# Sheet2-power.net
KiCad netlist of a schematic drawn in Altium Designer
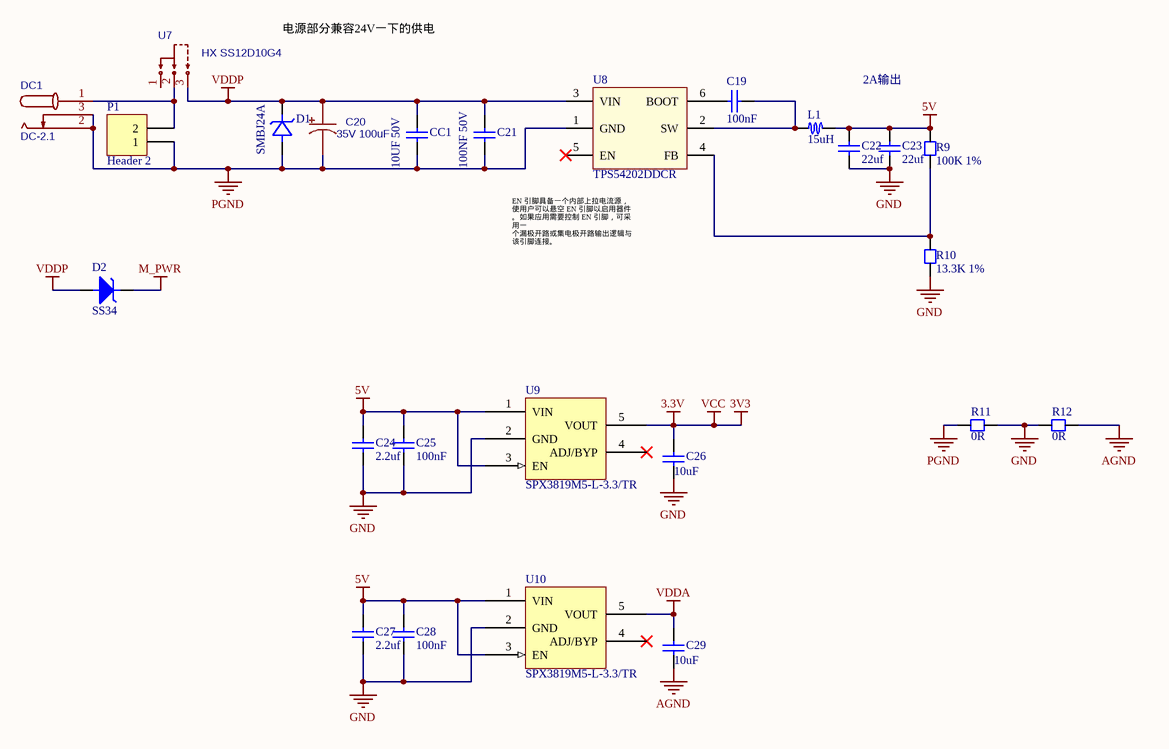
[diagram p0: Sheet2-power.SchDoc]

(export (version "E")
  (design (tool "Eeschema 10.0.6"))
  (components
    (comp (ref "C19")
      (value "100nF")
      (footprint "CC1608-0603")
      (description "0603封装的电容")
      (fields (field (name "PUBLISHER") "Altium Limited"))
      (libsource (lib "base") (part "Cap Chip 0603"))
    )
    (comp (ref "C20")
      (value "35V 100uF")
      (footprint "CAP-SMD_D6.3")
      (description "铝点解电容")
      (fields
        (field (name "BOM_SUPPLIER PART") "C413527")
        (field (name "BOM_MANUFACTURER PART") "EEEFP1C681AP")
        (field (name "CONTRIBUTOR") "LCSC")
      )
      (libsource (lib "base") (part "Cap ECAP SMD"))
    )
    (comp (ref "C21")
      (value "100NF 50V")
      (footprint "CC1608-0603")
      (description "0603封装的电容")
      (fields (field (name "PUBLISHER") "Altium Limited"))
      (libsource (lib "base") (part "Cap Chip 0603"))
    )
    (comp (ref "C22")
      (value "22uf")
      (footprint "CC1608-0603")
      (description "0603封装的电容")
      (fields (field (name "PUBLISHER") "Altium Limited"))
      (libsource (lib "base") (part "Cap Chip 0603"))
    )
    (comp (ref "C23")
      (value "22uf")
      (footprint "CC1608-0603")
      (description "0603封装的电容")
      (fields (field (name "PUBLISHER") "Altium Limited"))
      (libsource (lib "base") (part "Cap Chip 0603"))
    )
    (comp (ref "C24")
      (value "2.2uf")
      (footprint "CC1608-0603")
      (description "0603封装的电容")
      (fields (field (name "PUBLISHER") "Altium Limited"))
      (libsource (lib "base") (part "Cap Chip 0603"))
    )
    (comp (ref "C25")
      (value "100nF")
      (footprint "CC1608-0603")
      (description "0603封装的电容")
      (fields (field (name "PUBLISHER") "Altium Limited"))
      (libsource (lib "base") (part "Cap Chip 0603"))
    )
    (comp (ref "C26")
      (value "10uF")
      (footprint "CC1608-0603")
      (description "贴片电容")
      (libsource (lib "tianxiaohua_Schlib") (part "Chip capacitor"))
    )
    (comp (ref "C27")
      (value "2.2uf")
      (footprint "CC1608-0603")
      (description "0603封装的电容")
      (fields (field (name "PUBLISHER") "Altium Limited"))
      (libsource (lib "base") (part "Cap Chip 0603"))
    )
    (comp (ref "C28")
      (value "100nF")
      (footprint "CC1608-0603")
      (description "0603封装的电容")
      (fields (field (name "PUBLISHER") "Altium Limited"))
      (libsource (lib "base") (part "Cap Chip 0603"))
    )
    (comp (ref "C29")
      (value "10uF")
      (footprint "CC1608-0603")
      (description "贴片电容")
      (libsource (lib "tianxiaohua_Schlib") (part "Chip capacitor"))
    )
    (comp (ref "CC1")
      (value "10UF 50V")
      (footprint "CC3216-1206")
      (description "Polarized Capacitor (Radial)")
      (fields (field (name "Comment") "Cap Chip 1206") (field (name "PUBLISHER") "Altium Limited"))
      (libsource (lib "base") (part "Cap Chip 1206"))
    )
    (comp (ref "D1")
      (value "SMBJ24A")
      (footprint "DO-214 AA")
      (description "TVS稳压二极管")
      (libsource (lib "transistor") (part "SMBJ18A"))
    )
    (comp (ref "D2")
      (value "SS34")
      (footprint "DO-214 AA")
      (description "肖特基二极管")
      (libsource (lib "transistor") (part "SS34"))
    )
    (comp (ref "DC1")
      (value "DC-2.1")
      (footprint "DC-IN-SMD_DC-050-25A")
      (description "DC贴片插座")
      (fields
        (field (name "BOM_SUPPLIER PART") "C707275")
        (field (name "BOM_MANUFACTURER PART") "DC-050-25A")
        (field (name "CONTRIBUTOR") "LCSC")
      )
      (libsource (lib "Connectors") (part "DC-050"))
    )
    (comp (ref "L1")
      (value "15uH")
      (footprint "Inductor-4018")
      (description "贴片电感 1206封装")
      (libsource (lib "base") (part "Inductor-4018"))
    )
    (comp (ref "P1")
      (value "Header 2")
      (footprint "HX2.54-2")
      (description "Header, 2-Pin")
      (fields (field (name "PUBLISHER") "Altium Limited"))
      (libsource (lib "Connectors") (part "Header 2"))
    )
    (comp (ref "R9")
      (value "100K 1%")
      (footprint "CR1608-0603")
      (description "0603封装电阻")
      (fields (field (name "PUBLISHER") "Altium Limited"))
      (libsource (lib "base") (part "Resistor Chip 0603"))
    )
    (comp (ref "R10")
      (value "13.3K 1%")
      (footprint "CR1608-0603")
      (description "0603封装电阻")
      (fields (field (name "PUBLISHER") "Altium Limited"))
      (libsource (lib "base") (part "Resistor Chip 0603"))
    )
    (comp (ref "R11")
      (value "0R")
      (footprint "CR1608-0603")
      (description "0603封装电阻")
      (fields (field (name "PUBLISHER") "Altium Limited"))
      (libsource (lib "") (part "Resistor Chip 0603_1"))
    )
    (comp (ref "R12")
      (value "0R")
      (footprint "CR1608-0603")
      (description "0603封装电阻")
      (fields (field (name "PUBLISHER") "Altium Limited"))
      (libsource (lib "") (part "Resistor Chip 0603_1"))
    )
    (comp (ref "U7")
      (value "HX SS12D10G4")
      (footprint "SS12D10-G4")
      (fields (field (name "BOM_SUPPLIER PART") "C5149841") (field (name "CONTRIBUTOR") "lcsc"))
      (libsource (lib "Connectors") (part "SS12D10G4"))
    )
    (comp (ref "U8")
      (value "TPS54202DDCR")
      (footprint "SOT23-6")
      (description "同步降压转换器芯片 500Khz 4.2~28V输入，2A输出")
      (libsource (lib "power-chip") (part "TPS54202DDCR"))
    )
    (comp (ref "U9")
      (value "SPX3819M5-L-3.3/TR")
      (footprint "SOT23-5")
      (description "LDO 3.3V , SOT-23-5 500ma")
      (libsource (lib "power-chip") (part "SPX3819M5-L-3.3/TR"))
    )
    (comp (ref "U10")
      (value "SPX3819M5-L-3.3/TR")
      (footprint "SOT23-5")
      (description "LDO 3.3V , SOT-23-5 500ma")
      (libsource (lib "power-chip") (part "SPX3819M5-L-3.3/TR"))
    )
  )
  (nets
    (net (code "1") (name "3.3V") (class "Default")
      (node (ref "C26") (pin "1") (pinfunction "1_1") (pintype "passive"))
      (node (ref "U9") (pin "5") (pinfunction "VOUT_5") (pintype "passive"))
    )
    (net (code "2") (name "5V") (class "Default")
      (node (ref "C22") (pin "2") (pinfunction "2_2") (pintype "passive"))
      (node (ref "C23") (pin "2") (pinfunction "2_2") (pintype "passive"))
      (node (ref "C24") (pin "2") (pinfunction "2_2") (pintype "passive"))
      (node (ref "C25") (pin "2") (pinfunction "2_2") (pintype "passive"))
      (node (ref "C27") (pin "2") (pinfunction "2_2") (pintype "passive"))
      (node (ref "C28") (pin "2") (pinfunction "2_2") (pintype "passive"))
      (node (ref "L1") (pin "2") (pinfunction "2_2") (pintype "passive"))
      (node (ref "R9") (pin "2") (pinfunction "2_2") (pintype "passive"))
      (node (ref "U10") (pin "1") (pinfunction "VIN_1") (pintype "power_in"))
      (node (ref "U10") (pin "3") (pinfunction "EN_3") (pintype "input"))
      (node (ref "U9") (pin "1") (pinfunction "VIN_1") (pintype "power_in"))
      (node (ref "U9") (pin "3") (pinfunction "EN_3") (pintype "input"))
    )
    (net (code "3") (name "AGND") (class "Default")
      (node (ref "C29") (pin "2") (pinfunction "2_2") (pintype "passive"))
      (node (ref "R12") (pin "1") (pinfunction "1_1") (pintype "passive"))
    )
    (net (code "4") (name "GND") (class "Default")
      (node (ref "C22") (pin "1") (pinfunction "1_1") (pintype "passive"))
      (node (ref "C23") (pin "1") (pinfunction "1_1") (pintype "passive"))
      (node (ref "C24") (pin "1") (pinfunction "1_1") (pintype "passive"))
      (node (ref "C25") (pin "1") (pinfunction "1_1") (pintype "passive"))
      (node (ref "C26") (pin "2") (pinfunction "2_2") (pintype "passive"))
      (node (ref "C27") (pin "1") (pinfunction "1_1") (pintype "passive"))
      (node (ref "C28") (pin "1") (pinfunction "1_1") (pintype "passive"))
      (node (ref "R10") (pin "1") (pinfunction "1_1") (pintype "passive"))
      (node (ref "R11") (pin "1") (pinfunction "1_1") (pintype "passive"))
      (node (ref "R12") (pin "2") (pinfunction "2_2") (pintype "passive"))
      (node (ref "U10") (pin "2") (pinfunction "GND_2") (pintype "power_in"))
      (node (ref "U9") (pin "2") (pinfunction "GND_2") (pintype "power_in"))
    )
    (net (code "5") (name "M_PWR") (class "Default")
      (node (ref "D2") (pin "1") (pinfunction "K_1") (pintype "passive"))
    )
    (net (code "6") (name "Net-(DC1-Pad1)") (class "Default")
      (node (ref "DC1") (pin "1") (pinfunction "1_1") (pintype "passive"))
      (node (ref "P1") (pin "2") (pinfunction "2_2") (pintype "passive"))
      (node (ref "U7") (pin "2") (pinfunction "2_2") (pintype "passive"))
    )
    (net (code "7") (name "Net-(U8-BOOT)") (class "Default")
      (node (ref "C19") (pin "1") (pinfunction "1_1") (pintype "passive"))
      (node (ref "U8") (pin "6") (pinfunction "BOOT_6") (pintype "passive"))
    )
    (net (code "8") (name "Net-(U8-FB)") (class "Default")
      (node (ref "R10") (pin "2") (pinfunction "2_2") (pintype "passive"))
      (node (ref "R9") (pin "1") (pinfunction "1_1") (pintype "passive"))
      (node (ref "U8") (pin "4") (pinfunction "FB_4") (pintype "passive"))
    )
    (net (code "9") (name "Net-(U8-SW)") (class "Default")
      (node (ref "C19") (pin "2") (pinfunction "2_2") (pintype "passive"))
      (node (ref "L1") (pin "1") (pinfunction "1_1") (pintype "passive"))
      (node (ref "U8") (pin "2") (pinfunction "SW_2") (pintype "passive"))
    )
    (net (code "10") (name "PGND") (class "Default")
      (node (ref "C20") (pin "2") (pinfunction "2_2") (pintype "passive"))
      (node (ref "C21") (pin "1") (pinfunction "1_1") (pintype "passive"))
      (node (ref "CC1") (pin "1") (pinfunction "1_1") (pintype "passive"))
      (node (ref "D1") (pin "2") (pinfunction "A_2") (pintype "passive"))
      (node (ref "DC1") (pin "2") (pinfunction "2_2") (pintype "passive"))
      (node (ref "DC1") (pin "3") (pinfunction "3_3") (pintype "passive"))
      (node (ref "P1") (pin "1") (pinfunction "1_1") (pintype "passive"))
      (node (ref "R11") (pin "2") (pinfunction "2_2") (pintype "passive"))
      (node (ref "U8") (pin "1") (pinfunction "GND_1") (pintype "passive"))
    )
    (net (code "11") (name "VDDA") (class "Default")
      (node (ref "C29") (pin "1") (pinfunction "1_1") (pintype "passive"))
      (node (ref "U10") (pin "5") (pinfunction "VOUT_5") (pintype "passive"))
    )
    (net (code "12") (name "VDDP") (class "Default")
      (node (ref "C20") (pin "1") (pinfunction "1_1") (pintype "passive"))
      (node (ref "C21") (pin "2") (pinfunction "2_2") (pintype "passive"))
      (node (ref "CC1") (pin "2") (pinfunction "2_2") (pintype "passive"))
      (node (ref "D1") (pin "1") (pinfunction "K_1") (pintype "passive"))
      (node (ref "D2") (pin "2") (pinfunction "A_2") (pintype "passive"))
      (node (ref "U7") (pin "3") (pinfunction "3_3") (pintype "passive"))
      (node (ref "U8") (pin "3") (pinfunction "VIN_3") (pintype "passive"))
    )
    (net (code "13") (name "unconnected-(U7-Pad1)") (class "Default")
      (node (ref "U7") (pin "1") (pinfunction "1_1") (pintype "passive"))
    )
    (net (code "14") (name "unconnected-(U8-EN-Pad5)") (class "Default")
      (node (ref "U8") (pin "5") (pinfunction "EN_5") (pintype "passive+no_connect"))
    )
    (net (code "15") (name "unconnected-(U9-ADJ{slash}BYP-Pad4)") (class "Default")
      (node (ref "U9") (pin "4") (pinfunction "ADJ/BYP_4") (pintype "passive+no_connect"))
    )
    (net (code "16") (name "unconnected-(U10-ADJ{slash}BYP-Pad4)") (class "Default")
      (node (ref "U10") (pin "4") (pinfunction "ADJ/BYP_4") (pintype "passive+no_connect"))
    )
  )
)
